# s01_soc.net
KiCad netlist of a schematic drawn in Altium Designer
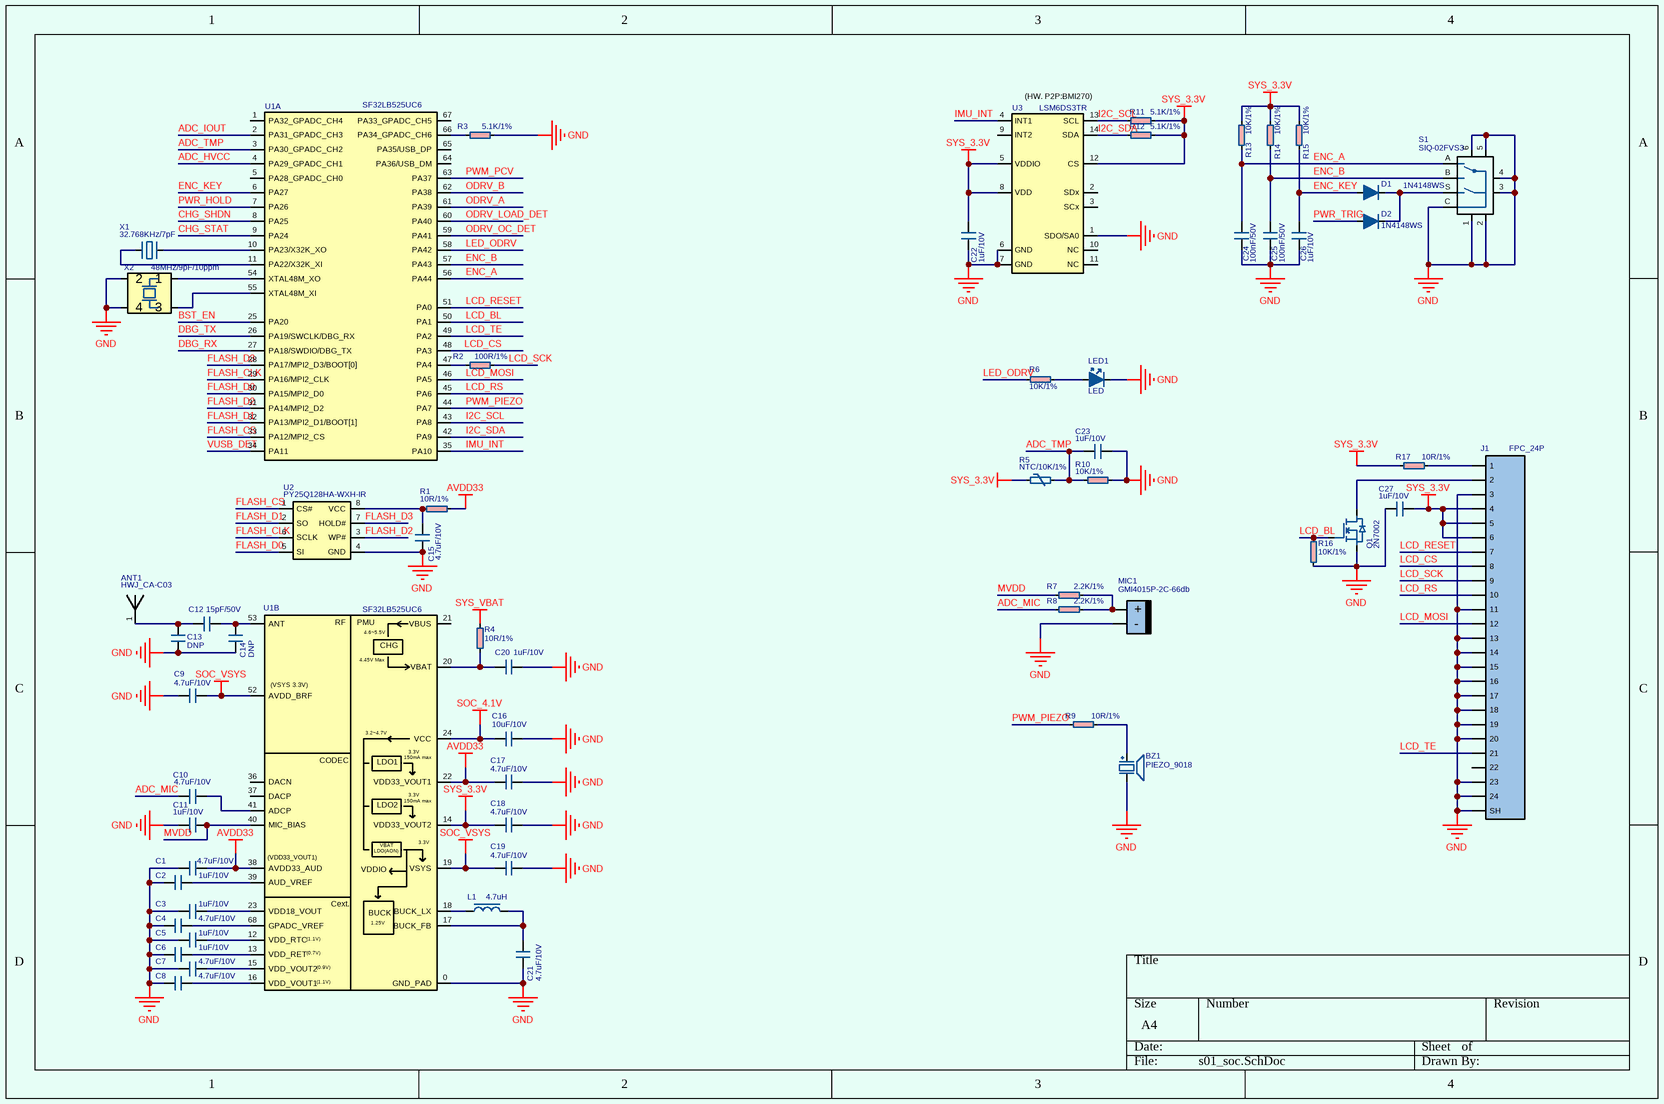
[diagram p0: s01_soc.SchDoc]

(export (version "E")
  (design (tool "Eeschema 10.0.6"))
  (components
    (comp (ref "ANT1")
      (value "HWJ_CA-C03")
      (footprint "ANT_2.4G_HWJ_CA-C03_MIRROR_OUTLINE")
      (description "T-net: 0R-3nH-0R")
      (libsource (lib "LibMySelf_SCHLIB") (part "ANT_2.4G_HWJ_CA-C03"))
    )
    (comp (ref "BZ1")
      (value "PIEZO_9018")
      (footprint "BUZZER_PIEZO_SMD_9X9X1.8MM_2PIN")
      (libsource (lib "LibMySelf_SCHLIB") (part "BUZZER_PIEZO_2PIN"))
    )
    (comp (ref "C1")
      (value "4.7uF/10V")
      (footprint "0402C")
      (libsource (lib "LibMySelf_SCHLIB") (part "CAP"))
    )
    (comp (ref "C2") (value "1uF/10V") (footprint "0402C") (libsource (lib "LibMySelf_SCHLIB") (part "CAP")))
    (comp (ref "C3") (value "1uF/10V") (footprint "0402C") (libsource (lib "LibMySelf_SCHLIB") (part "CAP")))
    (comp (ref "C4")
      (value "4.7uF/10V")
      (footprint "0402C")
      (libsource (lib "LibMySelf_SCHLIB") (part "CAP"))
    )
    (comp (ref "C5") (value "1uF/10V") (footprint "0402C") (libsource (lib "LibMySelf_SCHLIB") (part "CAP")))
    (comp (ref "C6") (value "1uF/10V") (footprint "0402C") (libsource (lib "LibMySelf_SCHLIB") (part "CAP")))
    (comp (ref "C7")
      (value "4.7uF/10V")
      (footprint "0402C")
      (libsource (lib "LibMySelf_SCHLIB") (part "CAP"))
    )
    (comp (ref "C8")
      (value "4.7uF/10V")
      (footprint "0402C")
      (libsource (lib "LibMySelf_SCHLIB") (part "CAP"))
    )
    (comp (ref "C9")
      (value "4.7uF/10V")
      (footprint "0402C")
      (libsource (lib "LibMySelf_SCHLIB") (part "CAP"))
    )
    (comp (ref "C10")
      (value "4.7uF/10V")
      (footprint "0402C")
      (libsource (lib "LibMySelf_SCHLIB") (part "CAP"))
    )
    (comp (ref "C11") (value "1uF/10V") (footprint "0402C") (libsource (lib "LibMySelf_SCHLIB") (part "CAP")))
    (comp (ref "C12")
      (value "15pF/50V")
      (footprint "0402C")
      (libsource (lib "LibMySelf_SCHLIB") (part "CAP"))
    )
    (comp (ref "C13") (value "DNP") (footprint "0402C") (libsource (lib "LibMySelf_SCHLIB") (part "CAP")))
    (comp (ref "C14") (value "DNP") (footprint "0402C") (libsource (lib "LibMySelf_SCHLIB") (part "CAP")))
    (comp (ref "C15")
      (value "4.7uF/10V")
      (footprint "0402C")
      (libsource (lib "LibMySelf_SCHLIB") (part "CAP"))
    )
    (comp (ref "C16")
      (value "10uF/10V")
      (footprint "0603C")
      (libsource (lib "LibMySelf_SCHLIB") (part "CAP"))
    )
    (comp (ref "C17")
      (value "4.7uF/10V")
      (footprint "0402C")
      (libsource (lib "LibMySelf_SCHLIB") (part "CAP"))
    )
    (comp (ref "C18")
      (value "4.7uF/10V")
      (footprint "0402C")
      (libsource (lib "LibMySelf_SCHLIB") (part "CAP"))
    )
    (comp (ref "C19")
      (value "4.7uF/10V")
      (footprint "0402C")
      (libsource (lib "LibMySelf_SCHLIB") (part "CAP"))
    )
    (comp (ref "C20") (value "1uF/10V") (footprint "0402C") (libsource (lib "LibMySelf_SCHLIB") (part "CAP")))
    (comp (ref "C21")
      (value "4.7uF/10V")
      (footprint "0402C")
      (libsource (lib "LibMySelf_SCHLIB") (part "CAP"))
    )
    (comp (ref "C22") (value "1uF/10V") (footprint "0402C") (libsource (lib "LibMySelf_SCHLIB") (part "CAP")))
    (comp (ref "C23") (value "1uF/10V") (footprint "0402C") (libsource (lib "LibMySelf_SCHLIB") (part "CAP")))
    (comp (ref "C24")
      (value "100nF/50V")
      (footprint "0402C")
      (libsource (lib "LibMySelf_SCHLIB") (part "CAP"))
    )
    (comp (ref "C25")
      (value "100nF/50V")
      (footprint "0402C")
      (libsource (lib "LibMySelf_SCHLIB") (part "CAP"))
    )
    (comp (ref "C26") (value "1uF/10V") (footprint "0402C") (libsource (lib "LibMySelf_SCHLIB") (part "CAP")))
    (comp (ref "C27") (value "1uF/10V") (footprint "0402C") (libsource (lib "LibMySelf_SCHLIB") (part "CAP")))
    (comp (ref "D1") (value "1N4148WS") (footprint "SOD323") (libsource (lib "LibMySelf_SCHLIB") (part "VD")))
    (comp (ref "D2") (value "1N4148WS") (footprint "SOD323") (libsource (lib "LibMySelf_SCHLIB") (part "VD")))
    (comp (ref "J1")
      (value "FPC_24P")
      (footprint "FPC_0.5MM_24P_H1.0_DNUP_MIRROR_FH34SRJ-24S-0.5SH")
      (libsource (lib "LibMySelf_SCHLIB") (part "CON24_FPC"))
    )
    (comp (ref "L1")
      (value "4.7uH")
      (footprint "INDUCTOR_0806_HD")
      (libsource (lib "LibMySelf_SCHLIB") (part "INDUCTOR"))
    )
    (comp (ref "LED1")
      (value "LED")
      (footprint "LED_0603")
      (libsource (lib "LibMySelf_SCHLIB") (part "LED_GENERAL"))
    )
    (comp (ref "MIC1")
      (value "GMI4015P-2C-66db")
      (footprint "MIC_DIP_F4_H1.5")
      (libsource (lib "LibMySelf_SCHLIB") (part "MIC_ELE"))
    )
    (comp (ref "Q1")
      (value "2N7002")
      (footprint "SOT23_MOS")
      (libsource (lib "LibMySelf_SCHLIB") (part "MOS_N"))
    )
    (comp (ref "R1") (value "10R/1%") (footprint "0402R") (libsource (lib "LibMySelf_SCHLIB") (part "RES")))
    (comp (ref "R2") (value "100R/1%") (footprint "0402R") (libsource (lib "LibMySelf_SCHLIB") (part "RES")))
    (comp (ref "R3") (value "5.1K/1%") (footprint "0402R") (libsource (lib "LibMySelf_SCHLIB") (part "RES")))
    (comp (ref "R4") (value "10R/1%") (footprint "0402R") (libsource (lib "LibMySelf_SCHLIB") (part "RES")))
    (comp (ref "R5")
      (value "NTC/10K/1%")
      (footprint "0402R")
      (libsource (lib "LibMySelf_SCHLIB") (part "NTC"))
    )
    (comp (ref "R6") (value "10K/1%") (footprint "0402R") (libsource (lib "LibMySelf_SCHLIB") (part "RES")))
    (comp (ref "R7") (value "2.2K/1%") (footprint "0402R") (libsource (lib "LibMySelf_SCHLIB") (part "RES")))
    (comp (ref "R8") (value "2.2K/1%") (footprint "0402R") (libsource (lib "LibMySelf_SCHLIB") (part "RES")))
    (comp (ref "R9") (value "10R/1%") (footprint "0603R") (libsource (lib "LibMySelf_SCHLIB") (part "RES")))
    (comp (ref "R10") (value "10K/1%") (footprint "0402R") (libsource (lib "LibMySelf_SCHLIB") (part "RES")))
    (comp (ref "R11") (value "5.1K/1%") (footprint "0402R") (libsource (lib "LibMySelf_SCHLIB") (part "RES")))
    (comp (ref "R12") (value "5.1K/1%") (footprint "0402R") (libsource (lib "LibMySelf_SCHLIB") (part "RES")))
    (comp (ref "R13") (value "10K/1%") (footprint "0402R") (libsource (lib "LibMySelf_SCHLIB") (part "RES")))
    (comp (ref "R14") (value "10K/1%") (footprint "0402R") (libsource (lib "LibMySelf_SCHLIB") (part "RES")))
    (comp (ref "R15") (value "10K/1%") (footprint "0402R") (libsource (lib "LibMySelf_SCHLIB") (part "RES")))
    (comp (ref "R16") (value "10K/1%") (footprint "0402R") (libsource (lib "LibMySelf_SCHLIB") (part "RES")))
    (comp (ref "R17") (value "10R/1%") (footprint "0402R") (libsource (lib "LibMySelf_SCHLIB") (part "RES")))
    (comp (ref "S1")
      (value "SIQ-02FVS3")
      (footprint "ENCODER_SMD_SIQ_02FVS3")
      (description "Rotary encoder in 15 detents with push function")
      (libsource (lib "LibMySelf_SCHLIB") (part "ENCODER_SIQ-02FVS3"))
    )
    (comp (ref "U1")
      (value "SF32LB525UC6")
      (footprint "QFN68_0.35_7X7_H0.9")
      (description "Li-ion power, 8MB psram, VSYS connect to VBAT")
      (libsource (lib "LibMySelf_SCHLIB") (part "SOC_SIFLI_SF32LB525UC6"))
    )
    (comp (ref "U2")
      (value "PY25Q128HA-WXH-IR")
      (footprint "DFN_5X6_1.27_EPAD_FLASH")
      (libsource (lib "LibMySelf_SCHLIB") (part "GD25Q32"))
    )
    (comp (ref "U3")
      (value "LSM6DS3TR")
      (footprint "LGA14_0.5_2.5X3_H0.9")
      (description "always-on 3D accelerometer and 3D gyroscope")
      (libsource (lib "LibMySelf_SCHLIB") (part "LSM6DS3"))
    )
    (comp (ref "X1")
      (value "32.768KHz/7pF")
      (footprint "XTAL_3215_2P")
      (description "Q13FC13500002")
      (libsource (lib "LibMySelf_SCHLIB") (part "XTAL"))
    )
    (comp (ref "X2")
      (value "48MHz/9pF/10ppm")
      (footprint "XTAL_2016_4P_N")
      (description "SX20Y048000B91T004")
      (libsource (lib "LibMySelf_SCHLIB") (part "XTAL_SMT_PASSIVE4PIN"))
    )
  )
  (nets
    (net (code "1") (name "/ADC_HVCC") (class "Default")
      (node (ref "U1") (pin "4") (pinfunction "PA29_GPADC_CH1_4") (pintype "passive"))
    )
    (net (code "2") (name "/ADC_IOUT") (class "Default")
      (node (ref "U1") (pin "2") (pinfunction "PA31_GPADC_CH3_2") (pintype "passive"))
    )
    (net (code "3") (name "/ADC_MIC") (class "Default")
      (node (ref "C10") (pin "1") (pinfunction "1_1") (pintype "passive"))
      (node (ref "R8") (pin "2") (pinfunction "2_2") (pintype "passive"))
    )
    (net (code "4") (name "/ADC_TMP") (class "Default")
      (node (ref "C23") (pin "2") (pinfunction "2_2") (pintype "passive"))
      (node (ref "R10") (pin "2") (pinfunction "2_2") (pintype "passive"))
      (node (ref "R5") (pin "2") (pinfunction "2_2") (pintype "passive"))
      (node (ref "U1") (pin "3") (pinfunction "PA30_GPADC_CH2_3") (pintype "passive"))
    )
    (net (code "5") (name "/BST_EN") (class "Default")
      (node (ref "U1") (pin "25") (pinfunction "PA20_25") (pintype "passive"))
    )
    (net (code "6") (name "/CHG_SHDN") (class "Default")
      (node (ref "U1") (pin "8") (pinfunction "PA25_8") (pintype "passive"))
    )
    (net (code "7") (name "/CHG_STAT") (class "Default")
      (node (ref "U1") (pin "9") (pinfunction "PA24_9") (pintype "passive"))
    )
    (net (code "8") (name "/DBG_RX") (class "Default")
      (node (ref "U1") (pin "27") (pinfunction "PA18/SWDIO/DBG_TX_27") (pintype "passive"))
    )
    (net (code "9") (name "/DBG_TX") (class "Default")
      (node (ref "U1") (pin "26") (pinfunction "PA19/SWCLK/DBG_RX_26") (pintype "passive"))
    )
    (net (code "10") (name "/ENC_A") (class "Default")
      (node (ref "C24") (pin "2") (pinfunction "2_2") (pintype "passive"))
      (node (ref "R13") (pin "1") (pinfunction "1_1") (pintype "passive"))
      (node (ref "S1") (pin "A") (pinfunction "A_A") (pintype "passive"))
      (node (ref "U1") (pin "56") (pinfunction "PA44_56") (pintype "passive"))
    )
    (net (code "11") (name "/ENC_B") (class "Default")
      (node (ref "C25") (pin "2") (pinfunction "2_2") (pintype "passive"))
      (node (ref "R14") (pin "1") (pinfunction "1_1") (pintype "passive"))
      (node (ref "S1") (pin "B") (pinfunction "B_B") (pintype "passive"))
      (node (ref "U1") (pin "57") (pinfunction "PA43_57") (pintype "passive"))
    )
    (net (code "12") (name "/ENC_KEY") (class "Default")
      (node (ref "C26") (pin "2") (pinfunction "2_2") (pintype "passive"))
      (node (ref "D1") (pin "1") (pinfunction "1_1") (pintype "passive"))
      (node (ref "R15") (pin "1") (pinfunction "1_1") (pintype "passive"))
      (node (ref "U1") (pin "6") (pinfunction "PA27_6") (pintype "passive"))
    )
    (net (code "13") (name "/FLASH_CLK") (class "Default")
      (node (ref "U1") (pin "29") (pinfunction "PA16/MPI2_CLK_29") (pintype "passive"))
      (node (ref "U2") (pin "6") (pinfunction "SCLK_6") (pintype "passive"))
    )
    (net (code "14") (name "/FLASH_CS") (class "Default")
      (node (ref "U1") (pin "33") (pinfunction "PA12/MPI2_CS_33") (pintype "passive"))
      (node (ref "U2") (pin "1") (pinfunction "CS#_1") (pintype "passive"))
    )
    (net (code "15") (name "/FLASH_D0") (class "Default")
      (node (ref "U1") (pin "30") (pinfunction "PA15/MPI2_D0_30") (pintype "passive"))
      (node (ref "U2") (pin "5") (pinfunction "SI_5") (pintype "passive"))
    )
    (net (code "16") (name "/FLASH_D1") (class "Default")
      (node (ref "U1") (pin "32") (pinfunction "PA13/MPI2_D1/BOOT[1]_32") (pintype "passive"))
      (node (ref "U2") (pin "2") (pinfunction "SO_2") (pintype "passive"))
    )
    (net (code "17") (name "/FLASH_D2") (class "Default")
      (node (ref "U1") (pin "31") (pinfunction "PA14/MPI2_D2_31") (pintype "passive"))
      (node (ref "U2") (pin "3") (pinfunction "WP#_3") (pintype "passive"))
    )
    (net (code "18") (name "/FLASH_D3") (class "Default")
      (node (ref "U1") (pin "28") (pinfunction "PA17/MPI2_D3/BOOT[0]_28") (pintype "passive"))
      (node (ref "U2") (pin "7") (pinfunction "HOLD#_7") (pintype "passive"))
    )
    (net (code "19") (name "/I2C_SCL") (class "Default")
      (node (ref "R11") (pin "2") (pinfunction "2_2") (pintype "passive"))
      (node (ref "U1") (pin "43") (pinfunction "PA8_43") (pintype "passive"))
      (node (ref "U3") (pin "13") (pinfunction "SCL_13") (pintype "passive"))
    )
    (net (code "20") (name "/I2C_SDA") (class "Default")
      (node (ref "R12") (pin "2") (pinfunction "2_2") (pintype "passive"))
      (node (ref "U1") (pin "42") (pinfunction "PA9_42") (pintype "passive"))
      (node (ref "U3") (pin "14") (pinfunction "SDA_14") (pintype "passive"))
    )
    (net (code "21") (name "/IMU_INT") (class "Default")
      (node (ref "U1") (pin "35") (pinfunction "PA10_35") (pintype "passive"))
      (node (ref "U3") (pin "4") (pinfunction "INT1_4") (pintype "passive"))
    )
    (net (code "22") (name "/LCD_BL") (class "Default")
      (node (ref "Q1") (pin "G") (pinfunction "G_G") (pintype "passive"))
      (node (ref "R16") (pin "1") (pinfunction "1_1") (pintype "passive"))
      (node (ref "U1") (pin "50") (pinfunction "PA1_50") (pintype "passive"))
    )
    (net (code "23") (name "/LCD_CS") (class "Default")
      (node (ref "J1") (pin "8") (pinfunction "8_8") (pintype "passive"))
      (node (ref "U1") (pin "48") (pinfunction "PA3_48") (pintype "passive"))
    )
    (net (code "24") (name "/LCD_MOSI") (class "Default")
      (node (ref "J1") (pin "12") (pinfunction "12_12") (pintype "passive"))
      (node (ref "U1") (pin "46") (pinfunction "PA5_46") (pintype "passive"))
    )
    (net (code "25") (name "/LCD_RESET") (class "Default")
      (node (ref "J1") (pin "7") (pinfunction "7_7") (pintype "passive"))
      (node (ref "U1") (pin "51") (pinfunction "PA0_51") (pintype "passive"))
    )
    (net (code "26") (name "/LCD_RS") (class "Default")
      (node (ref "J1") (pin "10") (pinfunction "10_10") (pintype "passive"))
      (node (ref "U1") (pin "45") (pinfunction "PA6_45") (pintype "passive"))
    )
    (net (code "27") (name "/LCD_SCK") (class "Default")
      (node (ref "J1") (pin "9") (pinfunction "9_9") (pintype "passive"))
      (node (ref "R2") (pin "2") (pinfunction "2_2") (pintype "passive"))
    )
    (net (code "28") (name "/LCD_TE") (class "Default")
      (node (ref "J1") (pin "21") (pinfunction "21_21") (pintype "passive"))
      (node (ref "U1") (pin "49") (pinfunction "PA2_49") (pintype "passive"))
    )
    (net (code "29") (name "/LED_ODRV") (class "Default")
      (node (ref "R6") (pin "2") (pinfunction "2_2") (pintype "passive"))
      (node (ref "U1") (pin "58") (pinfunction "PA42_58") (pintype "passive"))
    )
    (net (code "30") (name "/MVDD") (class "Default")
      (node (ref "C11") (pin "2") (pinfunction "2_2") (pintype "passive"))
      (node (ref "R7") (pin "2") (pinfunction "2_2") (pintype "passive"))
      (node (ref "U1") (pin "40") (pinfunction "MIC_BIAS_40") (pintype "passive"))
    )
    (net (code "31") (name "/ODRV_A") (class "Default")
      (node (ref "U1") (pin "61") (pinfunction "PA39_61") (pintype "passive"))
    )
    (net (code "32") (name "/ODRV_B") (class "Default")
      (node (ref "U1") (pin "62") (pinfunction "PA38_62") (pintype "passive"))
    )
    (net (code "33") (name "/ODRV_LOAD_DET") (class "Default")
      (node (ref "U1") (pin "60") (pinfunction "PA40_60") (pintype "passive"))
    )
    (net (code "34") (name "/ODRV_OC_DET") (class "Default")
      (node (ref "U1") (pin "59") (pinfunction "PA41_59") (pintype "passive"))
    )
    (net (code "35") (name "/PWM_PCV") (class "Default")
      (node (ref "U1") (pin "63") (pinfunction "PA37_63") (pintype "passive"))
    )
    (net (code "36") (name "/PWM_PIEZO") (class "Default")
      (node (ref "R9") (pin "1") (pinfunction "1_1") (pintype "passive"))
      (node (ref "U1") (pin "44") (pinfunction "PA7_44") (pintype "passive"))
    )
    (net (code "37") (name "/PWR_HOLD") (class "Default")
      (node (ref "U1") (pin "7") (pinfunction "PA26_7") (pintype "passive"))
    )
    (net (code "38") (name "/PWR_TRIG") (class "Default")
      (node (ref "D2") (pin "1") (pinfunction "1_1") (pintype "passive"))
    )
    (net (code "39") (name "/VUSB_DET") (class "Default")
      (node (ref "U1") (pin "34") (pinfunction "PA11_34") (pintype "passive"))
    )
    (net (code "40") (name "AVDD33") (class "Default")
      (node (ref "C1") (pin "2") (pinfunction "2_2") (pintype "passive"))
      (node (ref "C17") (pin "1") (pinfunction "1_1") (pintype "passive"))
      (node (ref "R1") (pin "1") (pinfunction "1_1") (pintype "passive"))
      (node (ref "U1") (pin "22") (pinfunction "VDD33_VOUT1_22") (pintype "passive"))
      (node (ref "U1") (pin "38") (pinfunction "AVDD33_AUD_38") (pintype "passive"))
    )
    (net (code "41") (name "GND") (class "Default")
      (node (ref "BZ1") (pin "2") (pinfunction "2_2") (pintype "passive"))
      (node (ref "C1") (pin "1") (pinfunction "1_1") (pintype "passive"))
      (node (ref "C11") (pin "1") (pinfunction "1_1") (pintype "passive"))
      (node (ref "C13") (pin "2") (pinfunction "2_2") (pintype "passive"))
      (node (ref "C14") (pin "1") (pinfunction "1_1") (pintype "passive"))
      (node (ref "C15") (pin "1") (pinfunction "1_1") (pintype "passive"))
      (node (ref "C16") (pin "1") (pinfunction "1_1") (pintype "passive"))
      (node (ref "C17") (pin "2") (pinfunction "2_2") (pintype "passive"))
      (node (ref "C18") (pin "2") (pinfunction "2_2") (pintype "passive"))
      (node (ref "C19") (pin "2") (pinfunction "2_2") (pintype "passive"))
      (node (ref "C2") (pin "1") (pinfunction "1_1") (pintype "passive"))
      (node (ref "C20") (pin "1") (pinfunction "1_1") (pintype "passive"))
      (node (ref "C21") (pin "1") (pinfunction "1_1") (pintype "passive"))
      (node (ref "C22") (pin "1") (pinfunction "1_1") (pintype "passive"))
      (node (ref "C23") (pin "1") (pinfunction "1_1") (pintype "passive"))
      (node (ref "C24") (pin "1") (pinfunction "1_1") (pintype "passive"))
      (node (ref "C25") (pin "1") (pinfunction "1_1") (pintype "passive"))
      (node (ref "C26") (pin "1") (pinfunction "1_1") (pintype "passive"))
      (node (ref "C27") (pin "1") (pinfunction "1_1") (pintype "passive"))
      (node (ref "C3") (pin "1") (pinfunction "1_1") (pintype "passive"))
      (node (ref "C4") (pin "1") (pinfunction "1_1") (pintype "passive"))
      (node (ref "C5") (pin "1") (pinfunction "1_1") (pintype "passive"))
      (node (ref "C6") (pin "1") (pinfunction "1_1") (pintype "passive"))
      (node (ref "C7") (pin "1") (pinfunction "1_1") (pintype "passive"))
      (node (ref "C8") (pin "1") (pinfunction "1_1") (pintype "passive"))
      (node (ref "C9") (pin "1") (pinfunction "1_1") (pintype "passive"))
      (node (ref "J1") (pin "0") (pinfunction "SH_0") (pintype "passive"))
      (node (ref "J1") (pin "11") (pinfunction "11_11") (pintype "passive"))
      (node (ref "J1") (pin "13") (pinfunction "13_13") (pintype "passive"))
      (node (ref "J1") (pin "14") (pinfunction "14_14") (pintype "passive"))
      (node (ref "J1") (pin "15") (pinfunction "15_15") (pintype "passive"))
      (node (ref "J1") (pin "16") (pinfunction "16_16") (pintype "passive"))
      (node (ref "J1") (pin "17") (pinfunction "17_17") (pintype "passive"))
      (node (ref "J1") (pin "18") (pinfunction "18_18") (pintype "passive"))
      (node (ref "J1") (pin "19") (pinfunction "19_19") (pintype "passive"))
      (node (ref "J1") (pin "20") (pinfunction "20_20") (pintype "passive"))
      (node (ref "J1") (pin "23") (pinfunction "23_23") (pintype "passive"))
      (node (ref "J1") (pin "24") (pinfunction "24_24") (pintype "passive"))
      (node (ref "J1") (pin "3") (pinfunction "3_3") (pintype "passive"))
      (node (ref "LED1") (pin "2") (pinfunction "2_2") (pintype "passive"))
      (node (ref "MIC1") (pin "2") (pinfunction "-_2") (pintype "passive"))
      (node (ref "Q1") (pin "S") (pinfunction "S_S") (pintype "passive"))
      (node (ref "R10") (pin "1") (pinfunction "1_1") (pintype "passive"))
      (node (ref "R16") (pin "2") (pinfunction "2_2") (pintype "passive"))
      (node (ref "R3") (pin "2") (pinfunction "2_2") (pintype "passive"))
      (node (ref "S1") (pin "1") (pinfunction "1_1") (pintype "passive"))
      (node (ref "S1") (pin "2") (pinfunction "2_2") (pintype "passive"))
      (node (ref "S1") (pin "3") (pinfunction "3_3") (pintype "passive"))
      (node (ref "S1") (pin "4") (pinfunction "4_4") (pintype "passive"))
      (node (ref "S1") (pin "5") (pinfunction "5_5") (pintype "passive"))
      (node (ref "S1") (pin "6") (pinfunction "6_6") (pintype "passive"))
      (node (ref "S1") (pin "C") (pinfunction "C_C") (pintype "passive"))
      (node (ref "U1") (pin "0") (pinfunction "GND_PAD_0") (pintype "passive"))
      (node (ref "U2") (pin "4") (pinfunction "GND_4") (pintype "passive"))
      (node (ref "U3") (pin "1") (pinfunction "SDO/SA0_1") (pintype "passive"))
      (node (ref "U3") (pin "6") (pinfunction "GND_6") (pintype "passive"))
      (node (ref "U3") (pin "7") (pinfunction "GND_7") (pintype "passive"))
      (node (ref "X2") (pin "2") (pinfunction "2_2") (pintype "passive"))
      (node (ref "X2") (pin "4") (pinfunction "4_4") (pintype "passive"))
    )
    (net (code "42") (name "Net-(ANT1-ANT)") (class "Default")
      (node (ref "ANT1") (pin "1") (pinfunction "ANT_1") (pintype "passive"))
      (node (ref "C12") (pin "2") (pinfunction "2_2") (pintype "passive"))
      (node (ref "C13") (pin "1") (pinfunction "1_1") (pintype "passive"))
    )
    (net (code "43") (name "Net-(BZ1-Pad1)") (class "Default")
      (node (ref "BZ1") (pin "1") (pinfunction "1_1") (pintype "passive"))
      (node (ref "R9") (pin "2") (pinfunction "2_2") (pintype "passive"))
    )
    (net (code "44") (name "Net-(D1-Pad2)") (class "Default")
      (node (ref "D1") (pin "2") (pinfunction "2_2") (pintype "passive"))
      (node (ref "D2") (pin "2") (pinfunction "2_2") (pintype "passive"))
      (node (ref "S1") (pin "S") (pinfunction "S_S") (pintype "passive"))
    )
    (net (code "45") (name "Net-(J1-Pad1)") (class "Default")
      (node (ref "J1") (pin "1") (pinfunction "1_1") (pintype "passive"))
      (node (ref "R17") (pin "2") (pinfunction "2_2") (pintype "passive"))
    )
    (net (code "46") (name "Net-(J1-Pad2)") (class "Default")
      (node (ref "J1") (pin "2") (pinfunction "2_2") (pintype "passive"))
      (node (ref "Q1") (pin "D") (pinfunction "D_D") (pintype "passive"))
    )
    (net (code "47") (name "Net-(LED1-Pad1)") (class "Default")
      (node (ref "LED1") (pin "1") (pinfunction "1_1") (pintype "passive"))
      (node (ref "R6") (pin "1") (pinfunction "1_1") (pintype "passive"))
    )
    (net (code "48") (name "Net-(MIC1-+)") (class "Default")
      (node (ref "MIC1") (pin "1") (pinfunction "+_1") (pintype "passive"))
      (node (ref "R7") (pin "1") (pinfunction "1_1") (pintype "passive"))
      (node (ref "R8") (pin "1") (pinfunction "1_1") (pintype "passive"))
    )
    (net (code "49") (name "Net-(U1A-PA4)") (class "Default")
      (node (ref "R2") (pin "1") (pinfunction "1_1") (pintype "passive"))
      (node (ref "U1") (pin "47") (pinfunction "PA4_47") (pintype "passive"))
    )
    (net (code "50") (name "Net-(U1A-PA22{slash}X32K_XI)") (class "Default")
      (node (ref "U1") (pin "11") (pinfunction "PA22/X32K_XI_11") (pintype "passive"))
      (node (ref "X1") (pin "1") (pinfunction "1_1") (pintype "passive"))
    )
    (net (code "51") (name "Net-(U1A-PA23{slash}X32K_XO)") (class "Default")
      (node (ref "U1") (pin "10") (pinfunction "PA23/X32K_XO_10") (pintype "passive"))
      (node (ref "X1") (pin "2") (pinfunction "2_2") (pintype "passive"))
    )
    (net (code "52") (name "Net-(U1A-PA34_GPADC_CH6)") (class "Default")
      (node (ref "R3") (pin "1") (pinfunction "1_1") (pintype "passive"))
      (node (ref "U1") (pin "66") (pinfunction "PA34_GPADC_CH6_66") (pintype "passive"))
    )
    (net (code "53") (name "Net-(U1A-XTAL48M_XI)") (class "Default")
      (node (ref "U1") (pin "55") (pinfunction "XTAL48M_XI_55") (pintype "passive"))
      (node (ref "X2") (pin "3") (pinfunction "3_3") (pintype "passive"))
    )
    (net (code "54") (name "Net-(U1A-XTAL48M_XO)") (class "Default")
      (node (ref "U1") (pin "54") (pinfunction "XTAL48M_XO_54") (pintype "passive"))
      (node (ref "X2") (pin "1") (pinfunction "1_1") (pintype "passive"))
    )
    (net (code "55") (name "Net-(U1B-ADCP)") (class "Default")
      (node (ref "C10") (pin "2") (pinfunction "2_2") (pintype "passive"))
      (node (ref "U1") (pin "41") (pinfunction "ADCP_41") (pintype "passive"))
    )
    (net (code "56") (name "Net-(U1B-ANT)") (class "Default")
      (node (ref "C12") (pin "1") (pinfunction "1_1") (pintype "passive"))
      (node (ref "C14") (pin "2") (pinfunction "2_2") (pintype "passive"))
      (node (ref "U1") (pin "53") (pinfunction "ANT_53") (pintype "passive"))
    )
    (net (code "57") (name "Net-(U1B-AUD_VREF)") (class "Default")
      (node (ref "C2") (pin "2") (pinfunction "2_2") (pintype "passive"))
      (node (ref "U1") (pin "39") (pinfunction "AUD_VREF_39") (pintype "passive"))
    )
    (net (code "58") (name "Net-(U1B-BUCK_FB)") (class "Default")
      (node (ref "C21") (pin "2") (pinfunction "2_2") (pintype "passive"))
      (node (ref "L1") (pin "2") (pinfunction "2_2") (pintype "passive"))
      (node (ref "U1") (pin "17") (pinfunction "BUCK_FB_17") (pintype "passive"))
    )
    (net (code "59") (name "Net-(U1B-BUCK_LX)") (class "Default")
      (node (ref "L1") (pin "1") (pinfunction "1_1") (pintype "passive"))
      (node (ref "U1") (pin "18") (pinfunction "BUCK_LX_18") (pintype "passive"))
    )
    (net (code "60") (name "Net-(U1B-GPADC_VREF)") (class "Default")
      (node (ref "C4") (pin "2") (pinfunction "2_2") (pintype "passive"))
      (node (ref "U1") (pin "68") (pinfunction "GPADC_VREF_68") (pintype "passive"))
    )
    (net (code "61") (name "Net-(U1B-VBAT)") (class "Default")
      (node (ref "C20") (pin "2") (pinfunction "2_2") (pintype "passive"))
      (node (ref "R4") (pin "2") (pinfunction "2_2") (pintype "passive"))
      (node (ref "U1") (pin "20") (pinfunction "VBAT_20") (pintype "passive"))
    )
    (net (code "62") (name "Net-(U1B-VDD18_VOUT)") (class "Default")
      (node (ref "C3") (pin "2") (pinfunction "2_2") (pintype "passive"))
      (node (ref "U1") (pin "23") (pinfunction "VDD18_VOUT_23") (pintype "passive"))
    )
    (net (code "63") (name "Net-(U1B-VDD_RET)") (class "Default")
      (node (ref "C6") (pin "2") (pinfunction "2_2") (pintype "passive"))
      (node (ref "U1") (pin "13") (pinfunction "VDD_RET_13") (pintype "passive"))
    )
    (net (code "64") (name "Net-(U1B-VDD_RTC)") (class "Default")
      (node (ref "C5") (pin "2") (pinfunction "2_2") (pintype "passive"))
      (node (ref "U1") (pin "12") (pinfunction "VDD_RTC_12") (pintype "passive"))
    )
    (net (code "65") (name "Net-(U1B-VDD_VOUT1)") (class "Default")
      (node (ref "C8") (pin "2") (pinfunction "2_2") (pintype "passive"))
      (node (ref "U1") (pin "16") (pinfunction "VDD_VOUT1_16") (pintype "passive"))
    )
    (net (code "66") (name "Net-(U1B-VDD_VOUT2)") (class "Default")
      (node (ref "C7") (pin "2") (pinfunction "2_2") (pintype "passive"))
      (node (ref "U1") (pin "15") (pinfunction "VDD_VOUT2_15") (pintype "passive"))
    )
    (net (code "67") (name "Net-(U2-VCC)") (class "Default")
      (node (ref "C15") (pin "2") (pinfunction "2_2") (pintype "passive"))
      (node (ref "R1") (pin "2") (pinfunction "2_2") (pintype "passive"))
      (node (ref "U2") (pin "8") (pinfunction "VCC_8") (pintype "passive"))
    )
    (net (code "68") (name "SOC_4.1V") (class "Default")
      (node (ref "C16") (pin "2") (pinfunction "2_2") (pintype "passive"))
      (node (ref "U1") (pin "24") (pinfunction "VCC_24") (pintype "passive"))
    )
    (net (code "69") (name "SOC_VSYS") (class "Default")
      (node (ref "C19") (pin "1") (pinfunction "1_1") (pintype "passive"))
      (node (ref "C9") (pin "2") (pinfunction "2_2") (pintype "passive"))
      (node (ref "U1") (pin "19") (pinfunction "VSYS_19") (pintype "passive"))
      (node (ref "U1") (pin "52") (pinfunction "AVDD_BRF_52") (pintype "passive"))
    )
    (net (code "70") (name "SYS_3.3V") (class "Default")
      (node (ref "C18") (pin "1") (pinfunction "1_1") (pintype "passive"))
      (node (ref "C22") (pin "2") (pinfunction "2_2") (pintype "passive"))
      (node (ref "C27") (pin "2") (pinfunction "2_2") (pintype "passive"))
      (node (ref "J1") (pin "4") (pinfunction "4_4") (pintype "passive"))
      (node (ref "J1") (pin "5") (pinfunction "5_5") (pintype "passive"))
      (node (ref "J1") (pin "6") (pinfunction "6_6") (pintype "passive"))
      (node (ref "R11") (pin "1") (pinfunction "1_1") (pintype "passive"))
      (node (ref "R12") (pin "1") (pinfunction "1_1") (pintype "passive"))
      (node (ref "R13") (pin "2") (pinfunction "2_2") (pintype "passive"))
      (node (ref "R14") (pin "2") (pinfunction "2_2") (pintype "passive"))
      (node (ref "R15") (pin "2") (pinfunction "2_2") (pintype "passive"))
      (node (ref "R17") (pin "1") (pinfunction "1_1") (pintype "passive"))
      (node (ref "R5") (pin "1") (pinfunction "1_1") (pintype "passive"))
      (node (ref "U1") (pin "14") (pinfunction "VDD33_VOUT2_14") (pintype "passive"))
      (node (ref "U3") (pin "12") (pinfunction "CS_12") (pintype "passive"))
      (node (ref "U3") (pin "5") (pinfunction "VDDIO_5") (pintype "passive"))
      (node (ref "U3") (pin "8") (pinfunction "VDD_8") (pintype "passive"))
    )
    (net (code "71") (name "SYS_VBAT") (class "Default")
      (node (ref "R4") (pin "1") (pinfunction "1_1") (pintype "passive"))
    )
    (net (code "72") (name "unconnected-(J1-Pad22)") (class "Default")
      (node (ref "J1") (pin "22") (pinfunction "22_22") (pintype "passive"))
    )
    (net (code "73") (name "unconnected-(U1A-PA28_GPADC_CH0-Pad5)") (class "Default")
      (node (ref "U1") (pin "5") (pinfunction "PA28_GPADC_CH0_5") (pintype "passive"))
    )
    (net (code "74") (name "unconnected-(U1A-PA32_GPADC_CH4-Pad1)") (class "Default")
      (node (ref "U1") (pin "1") (pinfunction "PA32_GPADC_CH4_1") (pintype "passive"))
    )
    (net (code "75") (name "unconnected-(U1A-PA33_GPADC_CH5-Pad67)") (class "Default")
      (node (ref "U1") (pin "67") (pinfunction "PA33_GPADC_CH5_67") (pintype "passive"))
    )
    (net (code "76") (name "unconnected-(U1A-PA35{slash}USB_DP-Pad65)") (class "Default")
      (node (ref "U1") (pin "65") (pinfunction "PA35/USB_DP_65") (pintype "passive"))
    )
    (net (code "77") (name "unconnected-(U1A-PA36{slash}USB_DM-Pad64)") (class "Default")
      (node (ref "U1") (pin "64") (pinfunction "PA36/USB_DM_64") (pintype "passive"))
    )
    (net (code "78") (name "unconnected-(U1B-DACN-Pad36)") (class "Default")
      (node (ref "U1") (pin "36") (pinfunction "DACN_36") (pintype "passive"))
    )
    (net (code "79") (name "unconnected-(U1B-DACP-Pad37)") (class "Default")
      (node (ref "U1") (pin "37") (pinfunction "DACP_37") (pintype "passive"))
    )
    (net (code "80") (name "unconnected-(U1B-VBUS-Pad21)") (class "Default")
      (node (ref "U1") (pin "21") (pinfunction "VBUS_21") (pintype "passive"))
    )
    (net (code "81") (name "unconnected-(U3-INT2-Pad9)") (class "Default")
      (node (ref "U3") (pin "9") (pinfunction "INT2_9") (pintype "passive"))
    )
    (net (code "82") (name "unconnected-(U3-NC-Pad10)") (class "Default")
      (node (ref "U3") (pin "10") (pinfunction "NC_10") (pintype "passive"))
    )
    (net (code "83") (name "unconnected-(U3-NC-Pad11)") (class "Default")
      (node (ref "U3") (pin "11") (pinfunction "NC_11") (pintype "passive"))
    )
    (net (code "84") (name "unconnected-(U3-SCx-Pad3)") (class "Default")
      (node (ref "U3") (pin "3") (pinfunction "SCx_3") (pintype "passive"))
    )
    (net (code "85") (name "unconnected-(U3-SDx-Pad2)") (class "Default")
      (node (ref "U3") (pin "2") (pinfunction "SDx_2") (pintype "passive"))
    )
  )
)
